# zx81_SD_10.net
KiCad netlist of a schematic drawn in EAGLE
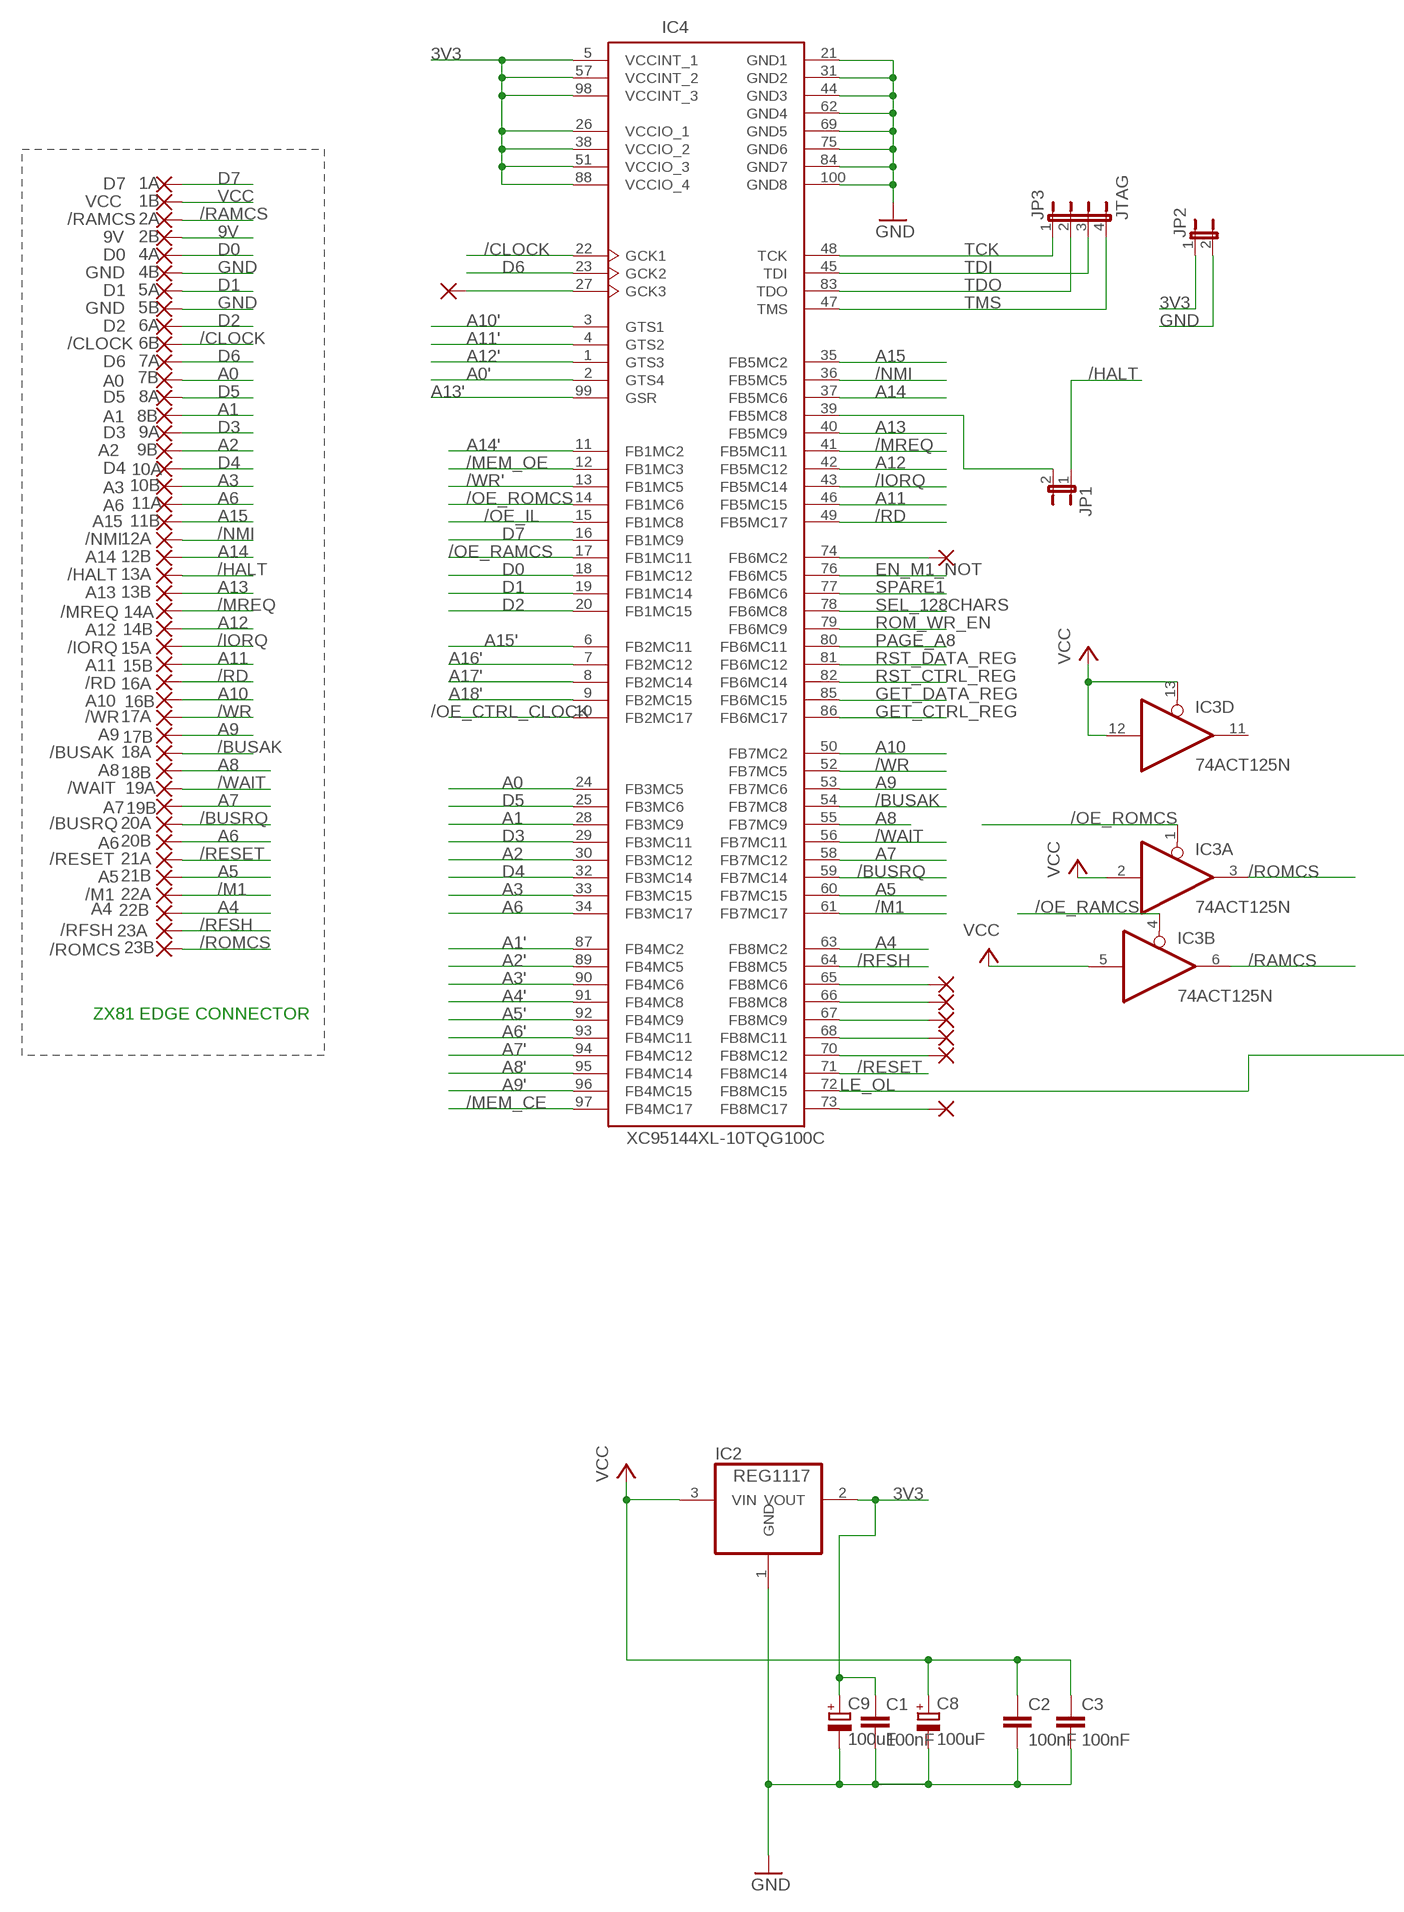
[diagram p0: schematic, sheet 1, part 1 of 2]
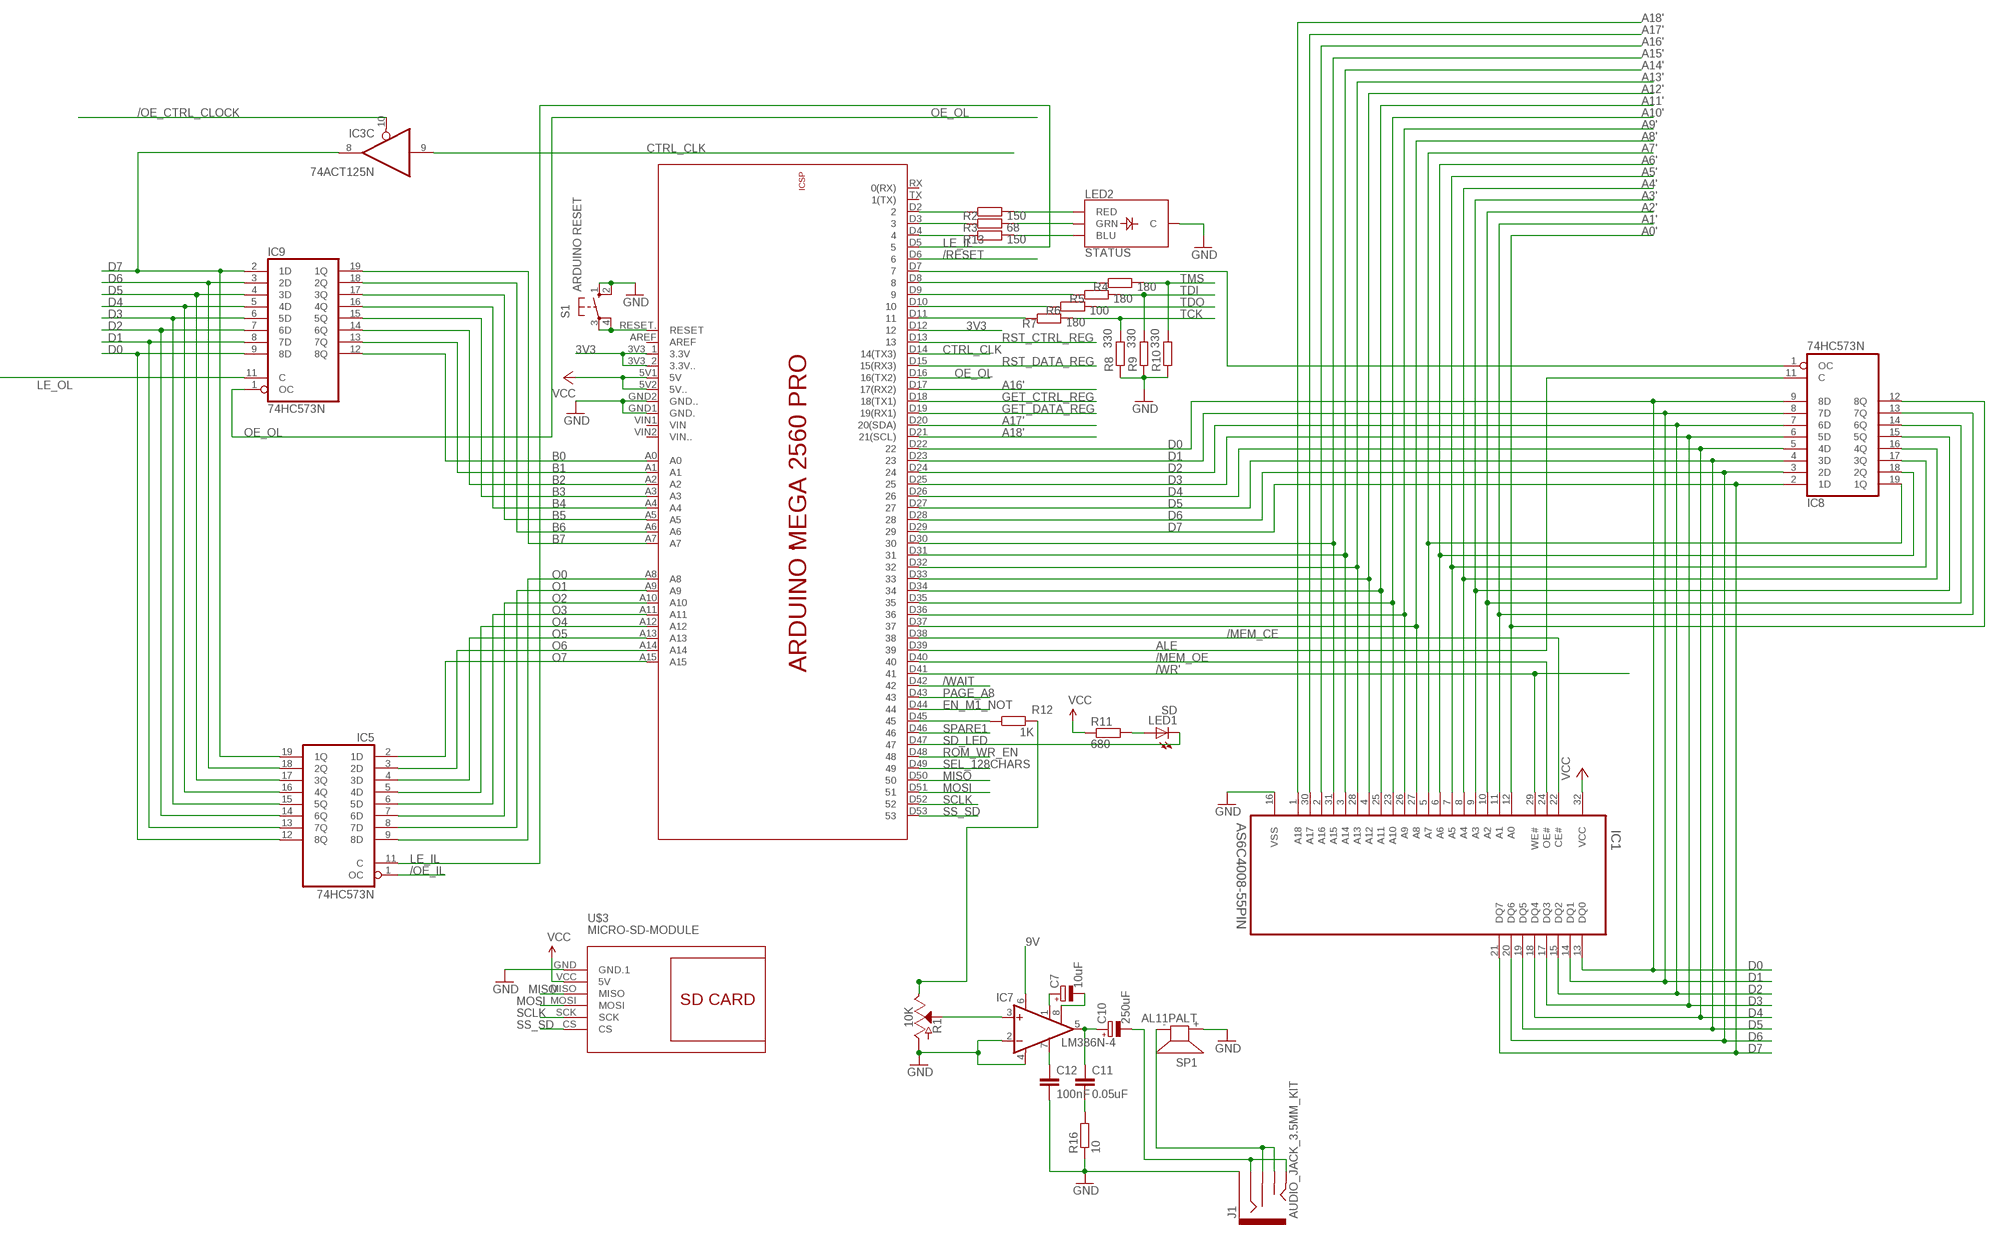
[diagram p1: schematic, sheet 1, part 2 of 2]

(export (version "E")
  (design (tool "Eeschema 10.0.6"))
  (components
    (comp (ref "1A")
      (value "D7")
      (footprint "eagle-import:EDGEPIN")
      (libsource (lib "eagle-import") (part "SMD2EDGEPIN"))
    )
    (comp (ref "1B")
      (value "VCC")
      (footprint "eagle-import:EDGEPIN")
      (libsource (lib "eagle-import") (part "SMD2EDGEPIN"))
    )
    (comp (ref "2A")
      (value "/RAMCS")
      (footprint "eagle-import:EDGEPIN")
      (libsource (lib "eagle-import") (part "SMD2EDGEPIN"))
    )
    (comp (ref "2B")
      (value "9V")
      (footprint "eagle-import:EDGEPIN")
      (libsource (lib "eagle-import") (part "SMD2EDGEPIN"))
    )
    (comp (ref "4A")
      (value "D0")
      (footprint "eagle-import:EDGEPIN")
      (libsource (lib "eagle-import") (part "SMD2EDGEPIN"))
    )
    (comp (ref "4B")
      (value "GND")
      (footprint "eagle-import:EDGEPIN")
      (libsource (lib "eagle-import") (part "SMD2EDGEPIN"))
    )
    (comp (ref "5A")
      (value "D1")
      (footprint "eagle-import:EDGEPIN")
      (libsource (lib "eagle-import") (part "SMD2EDGEPIN"))
    )
    (comp (ref "5B")
      (value "GND")
      (footprint "eagle-import:EDGEPIN")
      (libsource (lib "eagle-import") (part "SMD2EDGEPIN"))
    )
    (comp (ref "6A")
      (value "D2")
      (footprint "eagle-import:EDGEPIN")
      (libsource (lib "eagle-import") (part "SMD2EDGEPIN"))
    )
    (comp (ref "6B")
      (value "/CLOCK")
      (footprint "eagle-import:EDGEPIN")
      (libsource (lib "eagle-import") (part "SMD2EDGEPIN"))
    )
    (comp (ref "7A")
      (value "D6")
      (footprint "eagle-import:EDGEPIN")
      (libsource (lib "eagle-import") (part "SMD2EDGEPIN"))
    )
    (comp (ref "7B")
      (value "A0")
      (footprint "eagle-import:EDGEPIN")
      (libsource (lib "eagle-import") (part "SMD2EDGEPIN"))
    )
    (comp (ref "8A")
      (value "D5")
      (footprint "eagle-import:EDGEPIN")
      (libsource (lib "eagle-import") (part "SMD2EDGEPIN"))
    )
    (comp (ref "8B")
      (value "A1")
      (footprint "eagle-import:EDGEPIN")
      (libsource (lib "eagle-import") (part "SMD2EDGEPIN"))
    )
    (comp (ref "9A")
      (value "D3")
      (footprint "eagle-import:EDGEPIN")
      (libsource (lib "eagle-import") (part "SMD2EDGEPIN"))
    )
    (comp (ref "9B")
      (value "A2")
      (footprint "eagle-import:EDGEPIN")
      (libsource (lib "eagle-import") (part "SMD2EDGEPIN"))
    )
    (comp (ref "10A")
      (value "D4")
      (footprint "eagle-import:EDGEPIN")
      (libsource (lib "eagle-import") (part "SMD2EDGEPIN"))
    )
    (comp (ref "10B")
      (value "A3")
      (footprint "eagle-import:EDGEPIN")
      (libsource (lib "eagle-import") (part "SMD2EDGEPIN"))
    )
    (comp (ref "11A")
      (value "A6")
      (footprint "eagle-import:EDGEPIN")
      (libsource (lib "eagle-import") (part "SMD2EDGEPIN"))
    )
    (comp (ref "11B")
      (value "A15")
      (footprint "eagle-import:EDGEPIN")
      (libsource (lib "eagle-import") (part "SMD2EDGEPIN"))
    )
    (comp (ref "12A")
      (value "/NMI")
      (footprint "eagle-import:EDGEPIN")
      (libsource (lib "eagle-import") (part "SMD2EDGEPIN"))
    )
    (comp (ref "12B")
      (value "A14")
      (footprint "eagle-import:EDGEPIN")
      (libsource (lib "eagle-import") (part "SMD2EDGEPIN"))
    )
    (comp (ref "13A")
      (value "/HALT")
      (footprint "eagle-import:EDGEPIN")
      (libsource (lib "eagle-import") (part "SMD2EDGEPIN"))
    )
    (comp (ref "13B")
      (value "A13")
      (footprint "eagle-import:EDGEPIN")
      (libsource (lib "eagle-import") (part "SMD2EDGEPIN"))
    )
    (comp (ref "14A")
      (value "/MREQ")
      (footprint "eagle-import:EDGEPIN")
      (libsource (lib "eagle-import") (part "SMD2EDGEPIN"))
    )
    (comp (ref "14B")
      (value "A12")
      (footprint "eagle-import:EDGEPIN")
      (libsource (lib "eagle-import") (part "SMD2EDGEPIN"))
    )
    (comp (ref "15A")
      (value "/IORQ")
      (footprint "eagle-import:EDGEPIN")
      (libsource (lib "eagle-import") (part "SMD2EDGEPIN"))
    )
    (comp (ref "15B")
      (value "A11")
      (footprint "eagle-import:EDGEPIN")
      (libsource (lib "eagle-import") (part "SMD2EDGEPIN"))
    )
    (comp (ref "16A")
      (value "/RD")
      (footprint "eagle-import:EDGEPIN")
      (libsource (lib "eagle-import") (part "SMD2EDGEPIN"))
    )
    (comp (ref "16B")
      (value "A10")
      (footprint "eagle-import:EDGEPIN")
      (libsource (lib "eagle-import") (part "SMD2EDGEPIN"))
    )
    (comp (ref "17A")
      (value "/WR")
      (footprint "eagle-import:EDGEPIN")
      (libsource (lib "eagle-import") (part "SMD2EDGEPIN"))
    )
    (comp (ref "17B")
      (value "A9")
      (footprint "eagle-import:EDGEPIN")
      (libsource (lib "eagle-import") (part "SMD2EDGEPIN"))
    )
    (comp (ref "18A")
      (value "/BUSAK")
      (footprint "eagle-import:EDGEPIN")
      (libsource (lib "eagle-import") (part "SMD2EDGEPIN"))
    )
    (comp (ref "18B")
      (value "A8")
      (footprint "eagle-import:EDGEPIN")
      (libsource (lib "eagle-import") (part "SMD2EDGEPIN"))
    )
    (comp (ref "19A")
      (value "/WAIT")
      (footprint "eagle-import:EDGEPIN")
      (libsource (lib "eagle-import") (part "SMD2EDGEPIN"))
    )
    (comp (ref "19B")
      (value "A7")
      (footprint "eagle-import:EDGEPIN")
      (libsource (lib "eagle-import") (part "SMD2EDGEPIN"))
    )
    (comp (ref "20A")
      (value "/BUSRQ")
      (footprint "eagle-import:EDGEPIN")
      (libsource (lib "eagle-import") (part "SMD2EDGEPIN"))
    )
    (comp (ref "20B")
      (value "A6")
      (footprint "eagle-import:EDGEPIN")
      (libsource (lib "eagle-import") (part "SMD2EDGEPIN"))
    )
    (comp (ref "21A")
      (value "/RESET")
      (footprint "eagle-import:EDGEPIN")
      (libsource (lib "eagle-import") (part "SMD2EDGEPIN"))
    )
    (comp (ref "21B")
      (value "A5")
      (footprint "eagle-import:EDGEPIN")
      (libsource (lib "eagle-import") (part "SMD2EDGEPIN"))
    )
    (comp (ref "22A")
      (value "/M1")
      (footprint "eagle-import:EDGEPIN")
      (libsource (lib "eagle-import") (part "SMD2EDGEPIN"))
    )
    (comp (ref "22B")
      (value "A4")
      (footprint "eagle-import:EDGEPIN")
      (libsource (lib "eagle-import") (part "SMD2EDGEPIN"))
    )
    (comp (ref "23A")
      (value "/RFSH")
      (footprint "eagle-import:EDGEPIN")
      (libsource (lib "eagle-import") (part "SMD2EDGEPIN"))
    )
    (comp (ref "23B")
      (value "/ROMCS")
      (footprint "eagle-import:EDGEPIN")
      (libsource (lib "eagle-import") (part "SMD2EDGEPIN"))
    )
    (comp (ref "C1")
      (value "100nF")
      (footprint "eagle-import:C025-040X050")
      (libsource (lib "eagle-import") (part "C-EU025-040X050"))
    )
    (comp (ref "C2")
      (value "100nF")
      (footprint "eagle-import:C025-040X050")
      (libsource (lib "eagle-import") (part "C-EU025-040X050"))
    )
    (comp (ref "C3")
      (value "100nF")
      (footprint "eagle-import:C025-040X050")
      (libsource (lib "eagle-import") (part "C-EU025-040X050"))
    )
    (comp (ref "C7")
      (value "10uF")
      (footprint "eagle-import:E2-5")
      (libsource (lib "eagle-import") (part "CPOL-EUE2-5"))
    )
    (comp (ref "C8")
      (value "100uF")
      (footprint "eagle-import:E2-5")
      (libsource (lib "eagle-import") (part "CPOL-EUE2-5"))
    )
    (comp (ref "C9")
      (value "100uF")
      (footprint "eagle-import:E2-5")
      (libsource (lib "eagle-import") (part "CPOL-EUE2-5"))
    )
    (comp (ref "C10")
      (value "250uF")
      (footprint "eagle-import:E2-5")
      (libsource (lib "eagle-import") (part "CPOL-EUE2-5"))
    )
    (comp (ref "C11")
      (value "0.05uF")
      (footprint "eagle-import:C025-040X050")
      (libsource (lib "eagle-import") (part "C-EU025-040X050"))
    )
    (comp (ref "C12")
      (value "100nF")
      (footprint "eagle-import:C025-040X050")
      (libsource (lib "eagle-import") (part "C-EU025-040X050"))
    )
    (comp (ref "IC1")
      (value "AS6C4008-55PIN")
      (footprint "eagle-import:DIP1524W45P254L4203H406Q32")
      (fields (field (name "MF") "Alliance"))
      (libsource (lib "eagle-import") (part "AS6C4008-55PIN"))
    )
    (comp (ref "IC2")
      (value "REG1117")
      (footprint "eagle-import:SOT223")
      (libsource (lib "eagle-import") (part "REG1117"))
    )
    (comp (ref "IC3")
      (value "74ACT125N")
      (footprint "eagle-import:DIL14")
      (libsource (lib "eagle-import") (part "74125NACT"))
    )
    (comp (ref "IC4")
      (value "XC95144XL-10TQG100C")
      (footprint "eagle-import:TQFP100")
      (fields (field (name "MF") "Xilinx Inc."))
      (libsource (lib "eagle-import") (part "XC95144XL-10TQG100C"))
    )
    (comp (ref "IC5")
      (value "74HC573N")
      (footprint "eagle-import:DIL20")
      (libsource (lib "eagle-import") (part "74573NHC"))
    )
    (comp (ref "IC7")
      (value "LM386N-4")
      (footprint "eagle-import:DIL08")
      (libsource (lib "eagle-import") (part "LM386?-N4"))
    )
    (comp (ref "IC8")
      (value "74HC573N")
      (footprint "eagle-import:DIL20")
      (libsource (lib "eagle-import") (part "74573NHC"))
    )
    (comp (ref "IC9")
      (value "74HC573N")
      (footprint "eagle-import:DIL20")
      (libsource (lib "eagle-import") (part "74573NHC"))
    )
    (comp (ref "J1")
      (value "AUDIO_JACK_3.5MM_KIT")
      (footprint "eagle-import:AUDIO-JACK-KIT")
      (libsource (lib "eagle-import") (part "AUDIO_JACK_3.5MM_KIT"))
    )
    (comp (ref "JP1")
      (value "JP1E")
      (footprint "eagle-import:JP1")
      (libsource (lib "eagle-import") (part "JP1E"))
    )
    (comp (ref "JP2")
      (value "JP1E")
      (footprint "eagle-import:JP1")
      (libsource (lib "eagle-import") (part "JP1E"))
    )
    (comp (ref "JP3")
      (value "JTAG")
      (footprint "eagle-import:JP4")
      (libsource (lib "eagle-import") (part "JP4E"))
    )
    (comp (ref "LED1")
      (value "SD")
      (footprint "eagle-import:LED5MM")
      (libsource (lib "eagle-import") (part "LED5MM"))
    )
    (comp (ref "LED2")
      (value "STATUS")
      (footprint "eagle-import:LED-RGB-THRU")
      (libsource (lib "eagle-import") (part "LED-RGB-CCDIFFUSE"))
    )
    (comp (ref "PAD1")
      (value "1,6/0,8")
      (footprint "eagle-import:1,6_0,8")
      (libsource (lib "eagle-import") (part "1,6/0,8"))
    )
    (comp (ref "PAD2")
      (value "1,6/0,8")
      (footprint "eagle-import:1,6_0,8")
      (libsource (lib "eagle-import") (part "1,6/0,8"))
    )
    (comp (ref "PAD3")
      (value "1,6/0,8")
      (footprint "eagle-import:1,6_0,8")
      (libsource (lib "eagle-import") (part "1,6/0,8"))
    )
    (comp (ref "PAD4")
      (value "1,6/0,8")
      (footprint "eagle-import:1,6_0,8")
      (libsource (lib "eagle-import") (part "1,6/0,8"))
    )
    (comp (ref "PAD5")
      (value "1,6/0,8")
      (footprint "eagle-import:1,6_0,8")
      (libsource (lib "eagle-import") (part "1,6/0,8"))
    )
    (comp (ref "PAD6")
      (value "1,6/0,8")
      (footprint "eagle-import:1,6_0,8")
      (libsource (lib "eagle-import") (part "1,6/0,8"))
    )
    (comp (ref "PAD7")
      (value "1,6/0,8")
      (footprint "eagle-import:1,6_0,8")
      (libsource (lib "eagle-import") (part "1,6/0,8"))
    )
    (comp (ref "PAD8")
      (value "1,6/0,8")
      (footprint "eagle-import:1,6_0,8")
      (libsource (lib "eagle-import") (part "1,6/0,8"))
    )
    (comp (ref "R1")
      (value "10K")
      (footprint "eagle-import:POT-WHEEL")
      (libsource (lib "eagle-import") (part "POT"))
    )
    (comp (ref "R2")
      (value "150")
      (footprint "eagle-import:0204_7")
      (libsource (lib "eagle-import") (part "rcl_334_R-EU_0204/7"))
    )
    (comp (ref "R3")
      (value "68")
      (footprint "eagle-import:0204_7")
      (libsource (lib "eagle-import") (part "rcl_334_R-EU_0204/7"))
    )
    (comp (ref "R4")
      (value "180")
      (footprint "eagle-import:0204_7")
      (libsource (lib "eagle-import") (part "rcl_334_R-EU_0204/7"))
    )
    (comp (ref "R5")
      (value "180")
      (footprint "eagle-import:0204_7")
      (libsource (lib "eagle-import") (part "rcl_334_R-EU_0204/7"))
    )
    (comp (ref "R6")
      (value "100")
      (footprint "eagle-import:0204_7")
      (libsource (lib "eagle-import") (part "rcl_334_R-EU_0204/7"))
    )
    (comp (ref "R7")
      (value "180")
      (footprint "eagle-import:0204_7")
      (libsource (lib "eagle-import") (part "rcl_334_R-EU_0204/7"))
    )
    (comp (ref "R8")
      (value "330")
      (footprint "eagle-import:0204_7")
      (libsource (lib "eagle-import") (part "rcl_334_R-EU_0204/7"))
    )
    (comp (ref "R9")
      (value "330")
      (footprint "eagle-import:0204_7")
      (libsource (lib "eagle-import") (part "rcl_334_R-EU_0204/7"))
    )
    (comp (ref "R10")
      (value "330")
      (footprint "eagle-import:0204_7")
      (libsource (lib "eagle-import") (part "rcl_334_R-EU_0204/7"))
    )
    (comp (ref "R11")
      (value "680")
      (footprint "eagle-import:0204_7")
      (libsource (lib "eagle-import") (part "R-EU_0204/7"))
    )
    (comp (ref "R12")
      (value "1K")
      (footprint "eagle-import:0204_7")
      (libsource (lib "eagle-import") (part "R-EU_0204/7"))
    )
    (comp (ref "R13")
      (value "150")
      (footprint "eagle-import:0204_7")
      (libsource (lib "eagle-import") (part "rcl_334_R-EU_0204/7"))
    )
    (comp (ref "R16")
      (value "10")
      (footprint "eagle-import:0204_7")
      (libsource (lib "eagle-import") (part "R-EU_0204/7"))
    )
    (comp (ref "S1")
      (value "ARDUINO RESET")
      (footprint "eagle-import:B3F-10XX")
      (fields (field (name "MPN") "B3F-1000"))
      (libsource (lib "eagle-import") (part "10-XX"))
    )
    (comp (ref "SP1")
      (value "AL11PALT")
      (footprint "eagle-import:ALT")
      (libsource (lib "eagle-import") (part "AL11PALT"))
    )
    (comp (ref "U$2")
      (value "ARDUINO_MEGA2560_PRO")
      (footprint "eagle-import:ARDUINO_MEGA2560_PRO")
      (libsource (lib "eagle-import") (part "ARDUINO_MEGA2560_PRO"))
    )
    (comp (ref "U$3")
      (value "MICRO-SD-MODULE")
      (footprint "eagle-import:MICROSD-MODULE")
      (libsource (lib "eagle-import") (part "MICRO-SD-MODULE"))
    )
  )
  (nets
    (net (code "1") (name "/3V3") (class "Default")
      (node (ref "C1") (pin "1") (pinfunction "1_1") (pintype "passive"))
      (node (ref "C9") (pin "+") (pinfunction "+_+") (pintype "passive"))
      (node (ref "IC2") (pin "2") (pinfunction "VOUT_2") (pintype "output"))
      (node (ref "IC4") (pin "26") (pinfunction "VCCIO_1_26") (pintype "power_in"))
      (node (ref "IC4") (pin "38") (pinfunction "VCCIO_2_38") (pintype "power_in"))
      (node (ref "IC4") (pin "5") (pinfunction "VCCINT_1_5") (pintype "power_in"))
      (node (ref "IC4") (pin "51") (pinfunction "VCCIO_3_51") (pintype "power_in"))
      (node (ref "IC4") (pin "57") (pinfunction "VCCINT_2_57") (pintype "power_in"))
      (node (ref "IC4") (pin "88") (pinfunction "VCCIO_4_88") (pintype "power_in"))
      (node (ref "IC4") (pin "98") (pinfunction "VCCINT_3_98") (pintype "power_in"))
      (node (ref "JP2") (pin "1") (pinfunction "1_1") (pintype "passive"))
      (node (ref "U$2") (pin "3V3_1") (pinfunction "3.3V_3V3_1") (pintype "bidirectional"))
      (node (ref "U$2") (pin "3V3_2") (pinfunction "3.3V.._3V3_2") (pintype "bidirectional"))
      (node (ref "U$2") (pin "D12") (pinfunction "12_D12") (pintype "bidirectional"))
    )
    (net (code "2") (name "/9V") (class "Default")
      (node (ref "2B") (pin "1") (pinfunction "P_1") (pintype "passive"))
      (node (ref "IC7") (pin "6") (pinfunction "VS_6") (pintype "power_in"))
    )
    (net (code "3") (name "/A0") (class "Default")
      (node (ref "7B") (pin "1") (pinfunction "P_1") (pintype "passive"))
      (node (ref "IC4") (pin "24") (pinfunction "FB3MC5_24") (pintype "bidirectional"))
    )
    (net (code "4") (name "/A0'") (class "Default")
      (node (ref "IC1") (pin "12") (pinfunction "A0_12") (pintype "input"))
      (node (ref "IC4") (pin "2") (pinfunction "GTS4_2") (pintype "bidirectional"))
      (node (ref "IC8") (pin "12") (pinfunction "8Q_12") (pintype "tri_state"))
    )
    (net (code "5") (name "/A1") (class "Default")
      (node (ref "8B") (pin "1") (pinfunction "P_1") (pintype "passive"))
      (node (ref "IC4") (pin "28") (pinfunction "FB3MC9_28") (pintype "bidirectional"))
    )
    (net (code "6") (name "/A1'") (class "Default")
      (node (ref "IC1") (pin "11") (pinfunction "A1_11") (pintype "input"))
      (node (ref "IC4") (pin "87") (pinfunction "FB4MC2_87") (pintype "bidirectional"))
      (node (ref "IC8") (pin "13") (pinfunction "7Q_13") (pintype "tri_state"))
    )
    (net (code "7") (name "/A2") (class "Default")
      (node (ref "9B") (pin "1") (pinfunction "P_1") (pintype "passive"))
      (node (ref "IC4") (pin "30") (pinfunction "FB3MC12_30") (pintype "bidirectional"))
    )
    (net (code "8") (name "/A2'") (class "Default")
      (node (ref "IC1") (pin "10") (pinfunction "A2_10") (pintype "input"))
      (node (ref "IC4") (pin "89") (pinfunction "FB4MC5_89") (pintype "bidirectional"))
      (node (ref "IC8") (pin "14") (pinfunction "6Q_14") (pintype "tri_state"))
    )
    (net (code "9") (name "/A3") (class "Default")
      (node (ref "10B") (pin "1") (pinfunction "P_1") (pintype "passive"))
      (node (ref "IC4") (pin "33") (pinfunction "FB3MC15_33") (pintype "bidirectional"))
    )
    (net (code "10") (name "/A3'") (class "Default")
      (node (ref "IC1") (pin "9") (pinfunction "A3_9") (pintype "input"))
      (node (ref "IC4") (pin "90") (pinfunction "FB4MC6_90") (pintype "bidirectional"))
      (node (ref "IC8") (pin "15") (pinfunction "5Q_15") (pintype "tri_state"))
    )
    (net (code "11") (name "/A4") (class "Default")
      (node (ref "22B") (pin "1") (pinfunction "P_1") (pintype "passive"))
      (node (ref "IC4") (pin "63") (pinfunction "FB8MC2_63") (pintype "bidirectional"))
    )
    (net (code "12") (name "/A4'") (class "Default")
      (node (ref "IC1") (pin "8") (pinfunction "A4_8") (pintype "input"))
      (node (ref "IC4") (pin "91") (pinfunction "FB4MC8_91") (pintype "bidirectional"))
      (node (ref "IC8") (pin "16") (pinfunction "4Q_16") (pintype "tri_state"))
    )
    (net (code "13") (name "/A5") (class "Default")
      (node (ref "21B") (pin "1") (pinfunction "P_1") (pintype "passive"))
      (node (ref "IC4") (pin "60") (pinfunction "FB7MC15_60") (pintype "bidirectional"))
    )
    (net (code "14") (name "/A5'") (class "Default")
      (node (ref "IC1") (pin "7") (pinfunction "A5_7") (pintype "input"))
      (node (ref "IC4") (pin "92") (pinfunction "FB4MC9_92") (pintype "bidirectional"))
      (node (ref "IC8") (pin "17") (pinfunction "3Q_17") (pintype "tri_state"))
    )
    (net (code "15") (name "/A6") (class "Default")
      (node (ref "11A") (pin "1") (pinfunction "P_1") (pintype "passive"))
      (node (ref "20B") (pin "1") (pinfunction "P_1") (pintype "passive"))
      (node (ref "IC4") (pin "34") (pinfunction "FB3MC17_34") (pintype "bidirectional"))
    )
    (net (code "16") (name "/A6'") (class "Default")
      (node (ref "IC1") (pin "6") (pinfunction "A6_6") (pintype "input"))
      (node (ref "IC4") (pin "93") (pinfunction "FB4MC11_93") (pintype "bidirectional"))
      (node (ref "IC8") (pin "18") (pinfunction "2Q_18") (pintype "tri_state"))
    )
    (net (code "17") (name "/A7") (class "Default")
      (node (ref "19B") (pin "1") (pinfunction "P_1") (pintype "passive"))
      (node (ref "IC4") (pin "58") (pinfunction "FB7MC12_58") (pintype "bidirectional"))
    )
    (net (code "18") (name "/A7'") (class "Default")
      (node (ref "IC1") (pin "5") (pinfunction "A7_5") (pintype "input"))
      (node (ref "IC4") (pin "94") (pinfunction "FB4MC12_94") (pintype "bidirectional"))
      (node (ref "IC8") (pin "19") (pinfunction "1Q_19") (pintype "tri_state"))
    )
    (net (code "19") (name "/A8") (class "Default")
      (node (ref "18B") (pin "1") (pinfunction "P_1") (pintype "passive"))
      (node (ref "IC4") (pin "55") (pinfunction "FB7MC9_55") (pintype "bidirectional"))
    )
    (net (code "20") (name "/A8'") (class "Default")
      (node (ref "IC1") (pin "27") (pinfunction "A8_27") (pintype "input"))
      (node (ref "IC4") (pin "95") (pinfunction "FB4MC14_95") (pintype "bidirectional"))
      (node (ref "U$2") (pin "D37") (pinfunction "37_D37") (pintype "bidirectional"))
    )
    (net (code "21") (name "/A9") (class "Default")
      (node (ref "17B") (pin "1") (pinfunction "P_1") (pintype "passive"))
      (node (ref "IC4") (pin "53") (pinfunction "FB7MC6_53") (pintype "bidirectional"))
    )
    (net (code "22") (name "/A9'") (class "Default")
      (node (ref "IC1") (pin "26") (pinfunction "A9_26") (pintype "input"))
      (node (ref "IC4") (pin "96") (pinfunction "FB4MC15_96") (pintype "bidirectional"))
      (node (ref "U$2") (pin "D36") (pinfunction "36_D36") (pintype "bidirectional"))
    )
    (net (code "23") (name "/A10") (class "Default")
      (node (ref "16B") (pin "1") (pinfunction "P_1") (pintype "passive"))
      (node (ref "IC4") (pin "50") (pinfunction "FB7MC2_50") (pintype "bidirectional"))
    )
    (net (code "24") (name "/A10'") (class "Default")
      (node (ref "IC1") (pin "23") (pinfunction "A10_23") (pintype "input"))
      (node (ref "IC4") (pin "3") (pinfunction "GTS1_3") (pintype "bidirectional"))
      (node (ref "U$2") (pin "D35") (pinfunction "35_D35") (pintype "bidirectional"))
    )
    (net (code "25") (name "/A11") (class "Default")
      (node (ref "15B") (pin "1") (pinfunction "P_1") (pintype "passive"))
      (node (ref "IC4") (pin "46") (pinfunction "FB5MC15_46") (pintype "bidirectional"))
    )
    (net (code "26") (name "/A11'") (class "Default")
      (node (ref "IC1") (pin "25") (pinfunction "A11_25") (pintype "input"))
      (node (ref "IC4") (pin "4") (pinfunction "GTS2_4") (pintype "bidirectional"))
      (node (ref "U$2") (pin "D34") (pinfunction "34_D34") (pintype "bidirectional"))
    )
    (net (code "27") (name "/A12") (class "Default")
      (node (ref "14B") (pin "1") (pinfunction "P_1") (pintype "passive"))
      (node (ref "IC4") (pin "42") (pinfunction "FB5MC12_42") (pintype "bidirectional"))
    )
    (net (code "28") (name "/A12'") (class "Default")
      (node (ref "IC1") (pin "4") (pinfunction "A12_4") (pintype "input"))
      (node (ref "IC4") (pin "1") (pinfunction "GTS3_1") (pintype "bidirectional"))
      (node (ref "U$2") (pin "D33") (pinfunction "33_D33") (pintype "bidirectional"))
    )
    (net (code "29") (name "/A13") (class "Default")
      (node (ref "13B") (pin "1") (pinfunction "P_1") (pintype "passive"))
      (node (ref "IC4") (pin "40") (pinfunction "FB5MC9_40") (pintype "bidirectional"))
    )
    (net (code "30") (name "/A13'") (class "Default")
      (node (ref "IC1") (pin "28") (pinfunction "A13_28") (pintype "input"))
      (node (ref "IC4") (pin "99") (pinfunction "GSR_99") (pintype "bidirectional"))
      (node (ref "U$2") (pin "D32") (pinfunction "32_D32") (pintype "bidirectional"))
    )
    (net (code "31") (name "/A14") (class "Default")
      (node (ref "12B") (pin "1") (pinfunction "P_1") (pintype "passive"))
      (node (ref "IC4") (pin "37") (pinfunction "FB5MC6_37") (pintype "bidirectional"))
    )
    (net (code "32") (name "/A14'") (class "Default")
      (node (ref "IC1") (pin "3") (pinfunction "A14_3") (pintype "input"))
      (node (ref "IC4") (pin "11") (pinfunction "FB1MC2_11") (pintype "bidirectional"))
      (node (ref "U$2") (pin "D31") (pinfunction "31_D31") (pintype "bidirectional"))
    )
    (net (code "33") (name "/A15") (class "Default")
      (node (ref "11B") (pin "1") (pinfunction "P_1") (pintype "passive"))
      (node (ref "IC4") (pin "35") (pinfunction "FB5MC2_35") (pintype "bidirectional"))
    )
    (net (code "34") (name "/A15'") (class "Default")
      (node (ref "IC1") (pin "31") (pinfunction "A15_31") (pintype "input"))
      (node (ref "IC4") (pin "6") (pinfunction "FB2MC11_6") (pintype "bidirectional"))
      (node (ref "U$2") (pin "D30") (pinfunction "30_D30") (pintype "bidirectional"))
    )
    (net (code "35") (name "/A16'") (class "Default")
      (node (ref "IC1") (pin "2") (pinfunction "A16_2") (pintype "input"))
      (node (ref "IC4") (pin "7") (pinfunction "FB2MC12_7") (pintype "bidirectional"))
      (node (ref "U$2") (pin "D17") (pinfunction "17(RX2)_D17") (pintype "bidirectional"))
    )
    (net (code "36") (name "/A17'") (class "Default")
      (node (ref "IC1") (pin "30") (pinfunction "A17_30") (pintype "input"))
      (node (ref "IC4") (pin "8") (pinfunction "FB2MC14_8") (pintype "bidirectional"))
      (node (ref "U$2") (pin "D20") (pinfunction "20(SDA)_D20") (pintype "bidirectional"))
    )
    (net (code "37") (name "/A18'") (class "Default")
      (node (ref "IC1") (pin "1") (pinfunction "A18_1") (pintype "input"))
      (node (ref "IC4") (pin "9") (pinfunction "FB2MC15_9") (pintype "bidirectional"))
      (node (ref "U$2") (pin "D21") (pinfunction "21(SCL)_D21") (pintype "bidirectional"))
    )
    (net (code "38") (name "/ALE") (class "Default")
      (node (ref "IC8") (pin "11") (pinfunction "C_11") (pintype "input"))
      (node (ref "U$2") (pin "D39") (pinfunction "39_D39") (pintype "bidirectional"))
    )
    (net (code "39") (name "/B0") (class "Default")
      (node (ref "IC9") (pin "19") (pinfunction "1Q_19") (pintype "tri_state"))
      (node (ref "U$2") (pin "A7") (pinfunction "A7_A7") (pintype "bidirectional"))
    )
    (net (code "40") (name "/B1") (class "Default")
      (node (ref "IC9") (pin "18") (pinfunction "2Q_18") (pintype "tri_state"))
      (node (ref "U$2") (pin "A6") (pinfunction "A6_A6") (pintype "bidirectional"))
    )
    (net (code "41") (name "/B2") (class "Default")
      (node (ref "IC9") (pin "17") (pinfunction "3Q_17") (pintype "tri_state"))
      (node (ref "U$2") (pin "A5") (pinfunction "A5_A5") (pintype "bidirectional"))
    )
    (net (code "42") (name "/B3") (class "Default")
      (node (ref "IC9") (pin "16") (pinfunction "4Q_16") (pintype "tri_state"))
      (node (ref "U$2") (pin "A4") (pinfunction "A4_A4") (pintype "bidirectional"))
    )
    (net (code "43") (name "/B4") (class "Default")
      (node (ref "IC9") (pin "15") (pinfunction "5Q_15") (pintype "tri_state"))
      (node (ref "U$2") (pin "A3") (pinfunction "A3_A3") (pintype "bidirectional"))
    )
    (net (code "44") (name "/B5") (class "Default")
      (node (ref "IC9") (pin "14") (pinfunction "6Q_14") (pintype "tri_state"))
      (node (ref "U$2") (pin "A2") (pinfunction "A2_A2") (pintype "bidirectional"))
    )
    (net (code "45") (name "/B6") (class "Default")
      (node (ref "IC9") (pin "13") (pinfunction "7Q_13") (pintype "tri_state"))
      (node (ref "U$2") (pin "A1") (pinfunction "A1_A1") (pintype "bidirectional"))
    )
    (net (code "46") (name "/B7") (class "Default")
      (node (ref "IC9") (pin "12") (pinfunction "8Q_12") (pintype "tri_state"))
      (node (ref "U$2") (pin "A0") (pinfunction "A0_A0") (pintype "bidirectional"))
    )
    (net (code "47") (name "/CTRL_CLK") (class "Default")
      (node (ref "IC3") (pin "9") (pinfunction "I_9") (pintype "input"))
      (node (ref "U$2") (pin "D14") (pinfunction "14(TX3)_D14") (pintype "bidirectional"))
    )
    (net (code "48") (name "/D0") (class "Default")
      (node (ref "4A") (pin "1") (pinfunction "P_1") (pintype "passive"))
      (node (ref "IC1") (pin "13") (pinfunction "DQ0_13") (pintype "bidirectional"))
      (node (ref "IC4") (pin "18") (pinfunction "FB1MC12_18") (pintype "bidirectional"))
      (node (ref "IC5") (pin "12") (pinfunction "8Q_12") (pintype "tri_state"))
      (node (ref "IC8") (pin "9") (pinfunction "8D_9") (pintype "input"))
      (node (ref "IC9") (pin "9") (pinfunction "8D_9") (pintype "input"))
      (node (ref "U$2") (pin "D22") (pinfunction "22_D22") (pintype "bidirectional"))
    )
    (net (code "49") (name "/D1") (class "Default")
      (node (ref "5A") (pin "1") (pinfunction "P_1") (pintype "passive"))
      (node (ref "IC1") (pin "14") (pinfunction "DQ1_14") (pintype "bidirectional"))
      (node (ref "IC4") (pin "19") (pinfunction "FB1MC14_19") (pintype "bidirectional"))
      (node (ref "IC5") (pin "13") (pinfunction "7Q_13") (pintype "tri_state"))
      (node (ref "IC8") (pin "8") (pinfunction "7D_8") (pintype "input"))
      (node (ref "IC9") (pin "8") (pinfunction "7D_8") (pintype "input"))
      (node (ref "U$2") (pin "D23") (pinfunction "23_D23") (pintype "bidirectional"))
    )
    (net (code "50") (name "/D2") (class "Default")
      (node (ref "6A") (pin "1") (pinfunction "P_1") (pintype "passive"))
      (node (ref "IC1") (pin "15") (pinfunction "DQ2_15") (pintype "bidirectional"))
      (node (ref "IC4") (pin "20") (pinfunction "FB1MC15_20") (pintype "bidirectional"))
      (node (ref "IC5") (pin "14") (pinfunction "6Q_14") (pintype "tri_state"))
      (node (ref "IC8") (pin "7") (pinfunction "6D_7") (pintype "input"))
      (node (ref "IC9") (pin "7") (pinfunction "6D_7") (pintype "input"))
      (node (ref "U$2") (pin "D24") (pinfunction "24_D24") (pintype "bidirectional"))
    )
    (net (code "51") (name "/D3") (class "Default")
      (node (ref "9A") (pin "1") (pinfunction "P_1") (pintype "passive"))
      (node (ref "IC1") (pin "17") (pinfunction "DQ3_17") (pintype "bidirectional"))
      (node (ref "IC4") (pin "29") (pinfunction "FB3MC11_29") (pintype "bidirectional"))
      (node (ref "IC5") (pin "15") (pinfunction "5Q_15") (pintype "tri_state"))
      (node (ref "IC8") (pin "6") (pinfunction "5D_6") (pintype "input"))
      (node (ref "IC9") (pin "6") (pinfunction "5D_6") (pintype "input"))
      (node (ref "U$2") (pin "D25") (pinfunction "25_D25") (pintype "bidirectional"))
    )
    (net (code "52") (name "/D4") (class "Default")
      (node (ref "10A") (pin "1") (pinfunction "P_1") (pintype "passive"))
      (node (ref "IC1") (pin "18") (pinfunction "DQ4_18") (pintype "bidirectional"))
      (node (ref "IC4") (pin "32") (pinfunction "FB3MC14_32") (pintype "bidirectional"))
      (node (ref "IC5") (pin "16") (pinfunction "4Q_16") (pintype "tri_state"))
      (node (ref "IC8") (pin "5") (pinfunction "4D_5") (pintype "input"))
      (node (ref "IC9") (pin "5") (pinfunction "4D_5") (pintype "input"))
      (node (ref "U$2") (pin "D26") (pinfunction "26_D26") (pintype "bidirectional"))
    )
    (net (code "53") (name "/D5") (class "Default")
      (node (ref "8A") (pin "1") (pinfunction "P_1") (pintype "passive"))
      (node (ref "IC1") (pin "19") (pinfunction "DQ5_19") (pintype "bidirectional"))
      (node (ref "IC4") (pin "25") (pinfunction "FB3MC6_25") (pintype "bidirectional"))
      (node (ref "IC5") (pin "17") (pinfunction "3Q_17") (pintype "tri_state"))
      (node (ref "IC8") (pin "4") (pinfunction "3D_4") (pintype "input"))
      (node (ref "IC9") (pin "4") (pinfunction "3D_4") (pintype "input"))
      (node (ref "U$2") (pin "D27") (pinfunction "27_D27") (pintype "bidirectional"))
    )
    (net (code "54") (name "/D6") (class "Default")
      (node (ref "7A") (pin "1") (pinfunction "P_1") (pintype "passive"))
      (node (ref "IC1") (pin "20") (pinfunction "DQ6_20") (pintype "bidirectional"))
      (node (ref "IC4") (pin "23") (pinfunction "GCK2_23") (pintype "bidirectional"))
      (node (ref "IC5") (pin "18") (pinfunction "2Q_18") (pintype "tri_state"))
      (node (ref "IC8") (pin "3") (pinfunction "2D_3") (pintype "input"))
      (node (ref "IC9") (pin "3") (pinfunction "2D_3") (pintype "input"))
      (node (ref "U$2") (pin "D28") (pinfunction "28_D28") (pintype "bidirectional"))
    )
    (net (code "55") (name "/D7") (class "Default")
      (node (ref "1A") (pin "1") (pinfunction "P_1") (pintype "passive"))
      (node (ref "IC1") (pin "21") (pinfunction "DQ7_21") (pintype "bidirectional"))
      (node (ref "IC3") (pin "8") (pinfunction "O_8") (pintype "tri_state"))
      (node (ref "IC4") (pin "16") (pinfunction "FB1MC9_16") (pintype "bidirectional"))
      (node (ref "IC5") (pin "19") (pinfunction "1Q_19") (pintype "tri_state"))
      (node (ref "IC8") (pin "2") (pinfunction "1D_2") (pintype "input"))
      (node (ref "IC9") (pin "2") (pinfunction "1D_2") (pintype "input"))
      (node (ref "U$2") (pin "D29") (pinfunction "29_D29") (pintype "bidirectional"))
    )
    (net (code "56") (name "/EN_M1_NOT") (class "Default")
      (node (ref "IC4") (pin "76") (pinfunction "FB6MC5_76") (pintype "bidirectional"))
      (node (ref "U$2") (pin "D44") (pinfunction "44_D44") (pintype "bidirectional"))
    )
    (net (code "57") (name "/GET_CTRL_REG") (class "Default")
      (node (ref "IC4") (pin "86") (pinfunction "FB6MC17_86") (pintype "bidirectional"))
      (node (ref "U$2") (pin "D18") (pinfunction "18(TX1)_D18") (pintype "bidirectional"))
    )
    (net (code "58") (name "/GET_DATA_REG") (class "Default")
      (node (ref "IC4") (pin "85") (pinfunction "FB6MC15_85") (pintype "bidirectional"))
      (node (ref "U$2") (pin "D19") (pinfunction "19(RX1)_D19") (pintype "bidirectional"))
    )
    (net (code "59") (name "/LE_IL") (class "Default")
      (node (ref "IC5") (pin "11") (pinfunction "C_11") (pintype "input"))
      (node (ref "U$2") (pin "D5") (pinfunction "5_D5") (pintype "bidirectional"))
    )
    (net (code "60") (name "/LE_OL") (class "Default")
      (node (ref "IC4") (pin "72") (pinfunction "FB8MC15_72") (pintype "bidirectional"))
      (node (ref "IC9") (pin "11") (pinfunction "C_11") (pintype "input"))
    )
    (net (code "61") (name "/MISO") (class "Default")
      (node (ref "U$2") (pin "D50") (pinfunction "50_D50") (pintype "bidirectional"))
      (node (ref "U$3") (pin "MISO") (pinfunction "MISO_MISO") (pintype "bidirectional"))
    )
    (net (code "62") (name "/MOSI") (class "Default")
      (node (ref "U$2") (pin "D51") (pinfunction "51_D51") (pintype "bidirectional"))
      (node (ref "U$3") (pin "MOSI") (pinfunction "MOSI_MOSI") (pintype "bidirectional"))
    )
    (net (code "63") (name "/O0") (class "Default")
      (node (ref "IC5") (pin "2") (pinfunction "1D_2") (pintype "input"))
      (node (ref "U$2") (pin "A15") (pinfunction "A15_A15") (pintype "bidirectional"))
    )
    (net (code "64") (name "/O1") (class "Default")
      (node (ref "IC5") (pin "3") (pinfunction "2D_3") (pintype "input"))
      (node (ref "U$2") (pin "A14") (pinfunction "A14_A14") (pintype "bidirectional"))
    )
    (net (code "65") (name "/O2") (class "Default")
      (node (ref "IC5") (pin "4") (pinfunction "3D_4") (pintype "input"))
      (node (ref "U$2") (pin "A13") (pinfunction "A13_A13") (pintype "bidirectional"))
    )
    (net (code "66") (name "/O3") (class "Default")
      (node (ref "IC5") (pin "5") (pinfunction "4D_5") (pintype "input"))
      (node (ref "U$2") (pin "A12") (pinfunction "A12_A12") (pintype "bidirectional"))
    )
    (net (code "67") (name "/O4") (class "Default")
      (node (ref "IC5") (pin "6") (pinfunction "5D_6") (pintype "input"))
      (node (ref "U$2") (pin "A11") (pinfunction "A11_A11") (pintype "bidirectional"))
    )
    (net (code "68") (name "/O5") (class "Default")
      (node (ref "IC5") (pin "7") (pinfunction "6D_7") (pintype "input"))
      (node (ref "U$2") (pin "A10") (pinfunction "A10_A10") (pintype "bidirectional"))
    )
    (net (code "69") (name "/O6") (class "Default")
      (node (ref "IC5") (pin "8") (pinfunction "7D_8") (pintype "input"))
      (node (ref "U$2") (pin "A9") (pinfunction "A9_A9") (pintype "bidirectional"))
    )
    (net (code "70") (name "/O7") (class "Default")
      (node (ref "IC5") (pin "9") (pinfunction "8D_9") (pintype "input"))
      (node (ref "U$2") (pin "A8") (pinfunction "A8_A8") (pintype "bidirectional"))
    )
    (net (code "71") (name "/OE_OL") (class "Default")
      (node (ref "IC9") (pin "1") (pinfunction "OC_1") (pintype "input"))
      (node (ref "U$2") (pin "D16") (pinfunction "16(TX2)_D16") (pintype "bidirectional"))
    )
    (net (code "72") (name "/PAGE_A8") (class "Default")
      (node (ref "IC4") (pin "80") (pinfunction "FB6MC11_80") (pintype "bidirectional"))
      (node (ref "U$2") (pin "D43") (pinfunction "43_D43") (pintype "bidirectional"))
    )
    (net (code "73") (name "/ROM_WR_EN") (class "Default")
      (node (ref "IC4") (pin "79") (pinfunction "FB6MC9_79") (pintype "bidirectional"))
      (node (ref "U$2") (pin "D48") (pinfunction "48_D48") (pintype "bidirectional"))
    )
    (net (code "74") (name "/RST_CTRL_REG") (class "Default")
      (node (ref "IC4") (pin "82") (pinfunction "FB6MC14_82") (pintype "bidirectional"))
      (node (ref "U$2") (pin "D13") (pinfunction "13_D13") (pintype "bidirectional"))
    )
    (net (code "75") (name "/RST_DATA_REG") (class "Default")
      (node (ref "IC4") (pin "81") (pinfunction "FB6MC12_81") (pintype "bidirectional"))
      (node (ref "U$2") (pin "D15") (pinfunction "15(RX3)_D15") (pintype "bidirectional"))
    )
    (net (code "76") (name "/SCLK") (class "Default")
      (node (ref "U$2") (pin "D52") (pinfunction "52_D52") (pintype "bidirectional"))
      (node (ref "U$3") (pin "SCK") (pinfunction "SCK_SCK") (pintype "bidirectional"))
    )
    (net (code "77") (name "/SD_LED") (class "Default")
      (node (ref "LED1") (pin "K") (pinfunction "C_K") (pintype "passive"))
      (node (ref "U$2") (pin "D47") (pinfunction "47_D47") (pintype "bidirectional"))
    )
    (net (code "78") (name "/SEL_128CHARS") (class "Default")
      (node (ref "IC4") (pin "78") (pinfunction "FB6MC8_78") (pintype "bidirectional"))
      (node (ref "U$2") (pin "D49") (pinfunction "49_D49") (pintype "bidirectional"))
    )
    (net (code "79") (name "/SPARE1") (class "Default")
      (node (ref "IC4") (pin "77") (pinfunction "FB6MC6_77") (pintype "bidirectional"))
      (node (ref "U$2") (pin "D46") (pinfunction "46_D46") (pintype "bidirectional"))
    )
    (net (code "80") (name "/SS_SD") (class "Default")
      (node (ref "U$2") (pin "D53") (pinfunction "53_D53") (pintype "bidirectional"))
      (node (ref "U$3") (pin "CS") (pinfunction "CS_CS") (pintype "bidirectional"))
    )
    (net (code "81") (name "/TCK") (class "Default")
      (node (ref "IC4") (pin "48") (pinfunction "TCK_48") (pintype "passive"))
      (node (ref "JP3") (pin "1") (pinfunction "1_1") (pintype "passive"))
      (node (ref "R7") (pin "2") (pinfunction "2_2") (pintype "passive"))
      (node (ref "R8") (pin "2") (pinfunction "2_2") (pintype "passive"))
    )
    (net (code "82") (name "/TDI") (class "Default")
      (node (ref "IC4") (pin "45") (pinfunction "TDI_45") (pintype "passive"))
      (node (ref "JP3") (pin "3") (pinfunction "3_3") (pintype "passive"))
      (node (ref "R5") (pin "2") (pinfunction "2_2") (pintype "passive"))
      (node (ref "R9") (pin "2") (pinfunction "2_2") (pintype "passive"))
    )
    (net (code "83") (name "/TDO") (class "Default")
      (node (ref "IC4") (pin "83") (pinfunction "TDO_83") (pintype "passive"))
      (node (ref "JP3") (pin "2") (pinfunction "2_2") (pintype "passive"))
      (node (ref "R6") (pin "2") (pinfunction "2_2") (pintype "passive"))
    )
    (net (code "84") (name "/TMS") (class "Default")
      (node (ref "IC4") (pin "47") (pinfunction "TMS_47") (pintype "passive"))
      (node (ref "JP3") (pin "4") (pinfunction "4_4") (pintype "passive"))
      (node (ref "R10") (pin "2") (pinfunction "2_2") (pintype "passive"))
      (node (ref "R4") (pin "2") (pinfunction "2_2") (pintype "passive"))
    )
    (net (code "85") (name "/{slash}BUSAK") (class "Default")
      (node (ref "18A") (pin "1") (pinfunction "P_1") (pintype "passive"))
      (node (ref "IC4") (pin "54") (pinfunction "FB7MC8_54") (pintype "bidirectional"))
    )
    (net (code "86") (name "/{slash}BUSRQ") (class "Default")
      (node (ref "20A") (pin "1") (pinfunction "P_1") (pintype "passive"))
      (node (ref "IC4") (pin "59") (pinfunction "FB7MC14_59") (pintype "bidirectional"))
    )
    (net (code "87") (name "/{slash}CLOCK") (class "Default")
      (node (ref "6B") (pin "1") (pinfunction "P_1") (pintype "passive"))
      (node (ref "IC4") (pin "22") (pinfunction "GCK1_22") (pintype "bidirectional"))
    )
    (net (code "88") (name "/{slash}HALT") (class "Default")
      (node (ref "13A") (pin "1") (pinfunction "P_1") (pintype "passive"))
      (node (ref "JP1") (pin "1") (pinfunction "1_1") (pintype "passive"))
    )
    (net (code "89") (name "/{slash}IORQ") (class "Default")
      (node (ref "15A") (pin "1") (pinfunction "P_1") (pintype "passive"))
      (node (ref "IC4") (pin "43") (pinfunction "FB5MC14_43") (pintype "bidirectional"))
    )
    (net (code "90") (name "/{slash}M1") (class "Default")
      (node (ref "22A") (pin "1") (pinfunction "P_1") (pintype "passive"))
      (node (ref "IC4") (pin "61") (pinfunction "FB7MC17_61") (pintype "bidirectional"))
    )
    (net (code "91") (name "/{slash}MEM_CE") (class "Default")
      (node (ref "IC1") (pin "22") (pinfunction "CE#_22") (pintype "input"))
      (node (ref "IC4") (pin "97") (pinfunction "FB4MC17_97") (pintype "bidirectional"))
      (node (ref "U$2") (pin "D38") (pinfunction "38_D38") (pintype "bidirectional"))
    )
    (net (code "92") (name "/{slash}MEM_OE") (class "Default")
      (node (ref "IC1") (pin "24") (pinfunction "OE#_24") (pintype "input"))
      (node (ref "IC4") (pin "12") (pinfunction "FB1MC3_12") (pintype "bidirectional"))
      (node (ref "U$2") (pin "D40") (pinfunction "40_D40") (pintype "bidirectional"))
    )
    (net (code "93") (name "/{slash}MREQ") (class "Default")
      (node (ref "14A") (pin "1") (pinfunction "P_1") (pintype "passive"))
      (node (ref "IC4") (pin "41") (pinfunction "FB5MC11_41") (pintype "bidirectional"))
    )
    (net (code "94") (name "/{slash}NMI") (class "Default")
      (node (ref "12A") (pin "1") (pinfunction "P_1") (pintype "passive"))
      (node (ref "IC4") (pin "36") (pinfunction "FB5MC5_36") (pintype "bidirectional"))
    )
    (net (code "95") (name "/{slash}OE_CTRL_CLOCK") (class "Default")
      (node (ref "IC3") (pin "10") (pinfunction "OE_10") (pintype "input"))
      (node (ref "IC4") (pin "10") (pinfunction "FB2MC17_10") (pintype "bidirectional"))
    )
    (net (code "96") (name "/{slash}OE_IL") (class "Default")
      (node (ref "IC4") (pin "15") (pinfunction "FB1MC8_15") (pintype "bidirectional"))
      (node (ref "IC5") (pin "1") (pinfunction "OC_1") (pintype "input"))
    )
    (net (code "97") (name "/{slash}OE_RAMCS") (class "Default")
      (node (ref "IC3") (pin "4") (pinfunction "OE_4") (pintype "input"))
      (node (ref "IC4") (pin "17") (pinfunction "FB1MC11_17") (pintype "bidirectional"))
    )
    (net (code "98") (name "/{slash}OE_ROMCS") (class "Default")
      (node (ref "IC3") (pin "1") (pinfunction "OE_1") (pintype "input"))
      (node (ref "IC4") (pin "14") (pinfunction "FB1MC6_14") (pintype "bidirectional"))
    )
    (net (code "99") (name "/{slash}RAMCS") (class "Default")
      (node (ref "2A") (pin "1") (pinfunction "P_1") (pintype "passive"))
      (node (ref "IC3") (pin "6") (pinfunction "O_6") (pintype "tri_state"))
    )
    (net (code "100") (name "/{slash}RD") (class "Default")
      (node (ref "16A") (pin "1") (pinfunction "P_1") (pintype "passive"))
      (node (ref "IC4") (pin "49") (pinfunction "FB5MC17_49") (pintype "bidirectional"))
    )
    (net (code "101") (name "/{slash}RESET") (class "Default")
      (node (ref "21A") (pin "1") (pinfunction "P_1") (pintype "passive"))
      (node (ref "IC4") (pin "71") (pinfunction "FB8MC14_71") (pintype "bidirectional"))
      (node (ref "U$2") (pin "D6") (pinfunction "6_D6") (pintype "bidirectional"))
    )
    (net (code "102") (name "/{slash}RFSH") (class "Default")
      (node (ref "23A") (pin "1") (pinfunction "P_1") (pintype "passive"))
      (node (ref "IC4") (pin "64") (pinfunction "FB8MC5_64") (pintype "bidirectional"))
    )
    (net (code "103") (name "/{slash}ROMCS") (class "Default")
      (node (ref "23B") (pin "1") (pinfunction "P_1") (pintype "passive"))
      (node (ref "IC3") (pin "3") (pinfunction "O_3") (pintype "tri_state"))
    )
    (net (code "104") (name "/{slash}WAIT") (class "Default")
      (node (ref "19A") (pin "1") (pinfunction "P_1") (pintype "passive"))
      (node (ref "IC4") (pin "56") (pinfunction "FB7MC11_56") (pintype "bidirectional"))
      (node (ref "U$2") (pin "D42") (pinfunction "42_D42") (pintype "bidirectional"))
    )
    (net (code "105") (name "/{slash}WR") (class "Default")
      (node (ref "17A") (pin "1") (pinfunction "P_1") (pintype "passive"))
      (node (ref "IC4") (pin "52") (pinfunction "FB7MC5_52") (pintype "bidirectional"))
    )
    (net (code "106") (name "/{slash}WR'") (class "Default")
      (node (ref "IC1") (pin "29") (pinfunction "WE#_29") (pintype "input"))
      (node (ref "IC4") (pin "13") (pinfunction "FB1MC5_13") (pintype "bidirectional"))
      (node (ref "U$2") (pin "D41") (pinfunction "41_D41") (pintype "bidirectional"))
    )
    (net (code "107") (name "GND") (class "Default")
      (node (ref "4B") (pin "1") (pinfunction "P_1") (pintype "passive"))
      (node (ref "5B") (pin "1") (pinfunction "P_1") (pintype "passive"))
      (node (ref "C1") (pin "2") (pinfunction "2_2") (pintype "passive"))
      (node (ref "C12") (pin "2") (pinfunction "2_2") (pintype "passive"))
      (node (ref "C2") (pin "2") (pinfunction "2_2") (pintype "passive"))
      (node (ref "C3") (pin "2") (pinfunction "2_2") (pintype "passive"))
      (node (ref "C8") (pin "-") (pinfunction "-_-") (pintype "passive"))
      (node (ref "C9") (pin "-") (pinfunction "-_-") (pintype "passive"))
      (node (ref "IC1") (pin "16") (pinfunction "VSS_16") (pintype "power_in"))
      (node (ref "IC2") (pin "1") (pinfunction "GND_1") (pintype "power_in"))
      (node (ref "IC4") (pin "100") (pinfunction "GND8_100") (pintype "power_in"))
      (node (ref "IC4") (pin "21") (pinfunction "GND1_21") (pintype "power_in"))
      (node (ref "IC4") (pin "31") (pinfunction "GND2_31") (pintype "power_in"))
      (node (ref "IC4") (pin "44") (pinfunction "GND3_44") (pintype "power_in"))
      (node (ref "IC4") (pin "62") (pinfunction "GND4_62") (pintype "power_in"))
      (node (ref "IC4") (pin "69") (pinfunction "GND5_69") (pintype "power_in"))
      (node (ref "IC4") (pin "75") (pinfunction "GND6_75") (pintype "power_in"))
      (node (ref "IC4") (pin "84") (pinfunction "GND7_84") (pintype "power_in"))
      (node (ref "IC7") (pin "2") (pinfunction "-IN_2") (pintype "input"))
      (node (ref "IC7") (pin "4") (pinfunction "GND_4") (pintype "power_in"))
      (node (ref "J1") (pin "SLEEVE") (pinfunction "SLEEVE_SLEEVE") (pintype "bidirectional"))
      (node (ref "JP2") (pin "2") (pinfunction "2_2") (pintype "passive"))
      (node (ref "LED2") (pin "2") (pinfunction "C_2") (pintype "bidirectional"))
      (node (ref "R1") (pin "P$1") (pinfunction "A_P$1") (pintype "passive"))
      (node (ref "R10") (pin "1") (pinfunction "1_1") (pintype "passive"))
      (node (ref "R16") (pin "1") (pinfunction "1_1") (pintype "passive"))
      (node (ref "R8") (pin "1") (pinfunction "1_1") (pintype "passive"))
      (node (ref "R9") (pin "1") (pinfunction "1_1") (pintype "passive"))
      (node (ref "S1") (pin "1") (pinfunction "S_1") (pintype "passive"))
      (node (ref "S1") (pin "2") (pinfunction "S1_2") (pintype "passive"))
      (node (ref "SP1") (pin "+") (pinfunction "1_+") (pintype "passive"))
      (node (ref "U$2") (pin "GND1") (pinfunction "GND._GND1") (pintype "bidirectional"))
      (node (ref "U$2") (pin "GND2") (pinfunction "GND.._GND2") (pintype "bidirectional"))
      (node (ref "U$3") (pin "GND") (pinfunction "GND.1_GND") (pintype "power_in"))
    )
    (net (code "108") (name "Net-(C7-Pad+)") (class "Default")
      (node (ref "C7") (pin "+") (pinfunction "+_+") (pintype "passive"))
      (node (ref "IC7") (pin "1") (pinfunction "GAIN_1") (pintype "passive"))
    )
    (net (code "109") (name "Net-(C7-Pad-)") (class "Default")
      (node (ref "C7") (pin "-") (pinfunction "-_-") (pintype "passive"))
      (node (ref "IC7") (pin "8") (pinfunction "GAIN_8") (pintype "passive"))
    )
    (net (code "110") (name "Net-(C10-Pad-)") (class "Default")
      (node (ref "C10") (pin "-") (pinfunction "-_-") (pintype "passive"))
      (node (ref "J1") (pin "RING") (pinfunction "RING_RING") (pintype "bidirectional"))
      (node (ref "J1") (pin "TIP") (pinfunction "TIP_TIP") (pintype "bidirectional"))
    )
    (net (code "111") (name "Net-(C11-Pad2)") (class "Default")
      (node (ref "C11") (pin "2") (pinfunction "2_2") (pintype "passive"))
      (node (ref "R16") (pin "2") (pinfunction "2_2") (pintype "passive"))
    )
    (net (code "112") (name "Net-(IC4-FB5MC8)") (class "Default")
      (node (ref "IC4") (pin "39") (pinfunction "FB5MC8_39") (pintype "bidirectional"))
      (node (ref "JP1") (pin "2") (pinfunction "2_2") (pintype "passive"))
    )
    (net (code "113") (name "Net-(IC4-FB6MC2)") (class "Default")
      (node (ref "IC4") (pin "74") (pinfunction "FB6MC2_74") (pintype "bidirectional"))
      (node (ref "PAD8") (pin "1") (pinfunction "P_1") (pintype "passive"))
    )
    (net (code "114") (name "Net-(IC4-FB8MC6)") (class "Default")
      (node (ref "IC4") (pin "65") (pinfunction "FB8MC6_65") (pintype "bidirectional"))
      (node (ref "PAD2") (pin "1") (pinfunction "P_1") (pintype "passive"))
    )
    (net (code "115") (name "Net-(IC4-FB8MC8)") (class "Default")
      (node (ref "IC4") (pin "66") (pinfunction "FB8MC8_66") (pintype "bidirectional"))
      (node (ref "PAD3") (pin "1") (pinfunction "P_1") (pintype "passive"))
    )
    (net (code "116") (name "Net-(IC4-FB8MC9)") (class "Default")
      (node (ref "IC4") (pin "67") (pinfunction "FB8MC9_67") (pintype "bidirectional"))
      (node (ref "PAD4") (pin "1") (pinfunction "P_1") (pintype "passive"))
    )
    (net (code "117") (name "Net-(IC4-FB8MC11)") (class "Default")
      (node (ref "IC4") (pin "68") (pinfunction "FB8MC11_68") (pintype "bidirectional"))
      (node (ref "PAD5") (pin "1") (pinfunction "P_1") (pintype "passive"))
    )
    (net (code "118") (name "Net-(IC4-FB8MC12)") (class "Default")
      (node (ref "IC4") (pin "70") (pinfunction "FB8MC12_70") (pintype "bidirectional"))
      (node (ref "PAD7") (pin "1") (pinfunction "P_1") (pintype "passive"))
    )
    (net (code "119") (name "Net-(IC4-FB8MC17)") (class "Default")
      (node (ref "IC4") (pin "73") (pinfunction "FB8MC17_73") (pintype "bidirectional"))
      (node (ref "PAD6") (pin "1") (pinfunction "P_1") (pintype "passive"))
    )
    (net (code "120") (name "Net-(IC4-GCK3)") (class "Default")
      (node (ref "IC4") (pin "27") (pinfunction "GCK3_27") (pintype "bidirectional"))
      (node (ref "PAD1") (pin "1") (pinfunction "P_1") (pintype "passive"))
    )
    (net (code "121") (name "Net-(IC7-+IN)") (class "Default")
      (node (ref "IC7") (pin "3") (pinfunction "+IN_3") (pintype "input"))
      (node (ref "R1") (pin "P$3") (pinfunction "S_P$3") (pintype "passive"))
    )
    (net (code "122") (name "Net-(IC7-BYPASS)") (class "Default")
      (node (ref "C12") (pin "1") (pinfunction "1_1") (pintype "passive"))
      (node (ref "IC7") (pin "7") (pinfunction "BYPASS_7") (pintype "passive"))
    )
    (net (code "123") (name "Net-(IC7-OUT)") (class "Default")
      (node (ref "C10") (pin "+") (pinfunction "+_+") (pintype "passive"))
      (node (ref "C11") (pin "1") (pinfunction "1_1") (pintype "passive"))
      (node (ref "IC7") (pin "5") (pinfunction "OUT_5") (pintype "output"))
    )
    (net (code "124") (name "Net-(IC8A-OC)") (class "Default")
      (node (ref "IC8") (pin "1") (pinfunction "OC_1") (pintype "input"))
      (node (ref "U$2") (pin "D7") (pinfunction "7_D7") (pintype "bidirectional"))
    )
    (net (code "125") (name "Net-(LED1-PadA)") (class "Default")
      (node (ref "LED1") (pin "A") (pinfunction "A_A") (pintype "passive"))
      (node (ref "R11") (pin "2") (pinfunction "2_2") (pintype "passive"))
    )
    (net (code "126") (name "Net-(LED2-BLU)") (class "Default")
      (node (ref "LED2") (pin "3") (pinfunction "BLU_3") (pintype "bidirectional"))
      (node (ref "R13") (pin "2") (pinfunction "2_2") (pintype "passive"))
    )
    (net (code "127") (name "Net-(LED2-GRN)") (class "Default")
      (node (ref "LED2") (pin "4") (pinfunction "GRN_4") (pintype "bidirectional"))
      (node (ref "R3") (pin "2") (pinfunction "2_2") (pintype "passive"))
    )
    (net (code "128") (name "Net-(LED2-RED)") (class "Default")
      (node (ref "LED2") (pin "1") (pinfunction "RED_1") (pintype "bidirectional"))
      (node (ref "R2") (pin "2") (pinfunction "2_2") (pintype "passive"))
    )
    (net (code "129") (name "Net-(R1-E)") (class "Default")
      (node (ref "R1") (pin "P$2") (pinfunction "E_P$2") (pintype "passive"))
      (node (ref "R12") (pin "2") (pinfunction "2_2") (pintype "passive"))
    )
    (net (code "130") (name "Net-(S1-P)") (class "Default")
      (node (ref "S1") (pin "3") (pinfunction "P_3") (pintype "passive"))
      (node (ref "S1") (pin "4") (pinfunction "P1_4") (pintype "passive"))
      (node (ref "U$2") (pin "RESET.") (pinfunction "RESET_RESET.") (pintype "bidirectional"))
    )
    (net (code "131") (name "Net-(SP1-2)") (class "Default")
      (node (ref "J1") (pin "RSH") (pinfunction "RSH_RSH") (pintype "bidirectional"))
      (node (ref "J1") (pin "TSH") (pinfunction "TSH_TSH") (pintype "bidirectional"))
      (node (ref "SP1") (pin "-") (pinfunction "2_-") (pintype "passive"))
    )
    (net (code "132") (name "Net-(U$2-2)") (class "Default")
      (node (ref "R2") (pin "1") (pinfunction "1_1") (pintype "passive"))
      (node (ref "U$2") (pin "D2") (pinfunction "2_D2") (pintype "bidirectional"))
    )
    (net (code "133") (name "Net-(U$2-3)") (class "Default")
      (node (ref "R3") (pin "1") (pinfunction "1_1") (pintype "passive"))
      (node (ref "U$2") (pin "D3") (pinfunction "3_D3") (pintype "bidirectional"))
    )
    (net (code "134") (name "Net-(U$2-4)") (class "Default")
      (node (ref "R13") (pin "1") (pinfunction "1_1") (pintype "passive"))
      (node (ref "U$2") (pin "D4") (pinfunction "4_D4") (pintype "bidirectional"))
    )
    (net (code "135") (name "Net-(U$2-8)") (class "Default")
      (node (ref "R4") (pin "1") (pinfunction "1_1") (pintype "passive"))
      (node (ref "U$2") (pin "D8") (pinfunction "8_D8") (pintype "bidirectional"))
    )
    (net (code "136") (name "Net-(U$2-9)") (class "Default")
      (node (ref "R5") (pin "1") (pinfunction "1_1") (pintype "passive"))
      (node (ref "U$2") (pin "D9") (pinfunction "9_D9") (pintype "bidirectional"))
    )
    (net (code "137") (name "Net-(U$2-10)") (class "Default")
      (node (ref "R6") (pin "1") (pinfunction "1_1") (pintype "passive"))
      (node (ref "U$2") (pin "D10") (pinfunction "10_D10") (pintype "bidirectional"))
    )
    (net (code "138") (name "Net-(U$2-11)") (class "Default")
      (node (ref "R7") (pin "1") (pinfunction "1_1") (pintype "passive"))
      (node (ref "U$2") (pin "D11") (pinfunction "11_D11") (pintype "bidirectional"))
    )
    (net (code "139") (name "Net-(U$2-45)") (class "Default")
      (node (ref "R12") (pin "1") (pinfunction "1_1") (pintype "passive"))
      (node (ref "U$2") (pin "D45") (pinfunction "45_D45") (pintype "bidirectional"))
    )
    (net (code "140") (name "VCC") (class "Default")
      (node (ref "1B") (pin "1") (pinfunction "P_1") (pintype "passive"))
      (node (ref "C2") (pin "1") (pinfunction "1_1") (pintype "passive"))
      (node (ref "C3") (pin "1") (pinfunction "1_1") (pintype "passive"))
      (node (ref "C8") (pin "+") (pinfunction "+_+") (pintype "passive"))
      (node (ref "IC1") (pin "32") (pinfunction "VCC_32") (pintype "power_in"))
      (node (ref "IC2") (pin "3") (pinfunction "VIN_3") (pintype "input"))
      (node (ref "IC3") (pin "12") (pinfunction "I_12") (pintype "input"))
      (node (ref "IC3") (pin "13") (pinfunction "OE_13") (pintype "input"))
      (node (ref "IC3") (pin "2") (pinfunction "I_2") (pintype "input"))
      (node (ref "IC3") (pin "5") (pinfunction "I_5") (pintype "input"))
      (node (ref "R11") (pin "1") (pinfunction "1_1") (pintype "passive"))
      (node (ref "U$2") (pin "5V1") (pinfunction "5V_5V1") (pintype "bidirectional"))
      (node (ref "U$2") (pin "5V2") (pinfunction "5V.._5V2") (pintype "bidirectional"))
      (node (ref "U$3") (pin "VCC") (pinfunction "5V_VCC") (pintype "power_in"))
    )
    (net (code "141") (name "unconnected-(IC3D-O-Pad11)") (class "Default")
      (node (ref "IC3") (pin "11") (pinfunction "O_11") (pintype "tri_state"))
    )
    (net (code "142") (name "unconnected-(U$2-0(RX)-PadRX)") (class "Default")
      (node (ref "U$2") (pin "RX") (pinfunction "0(RX)_RX") (pintype "bidirectional"))
    )
    (net (code "143") (name "unconnected-(U$2-1(TX)-PadTX)") (class "Default")
      (node (ref "U$2") (pin "TX") (pinfunction "1(TX)_TX") (pintype "bidirectional"))
    )
    (net (code "144") (name "unconnected-(U$2-Pad+5V_)") (class "Default")
      (node (ref "U$2") (pin "+5V_") (pinfunction "+5V__+5V_") (pintype "bidirectional"))
    )
    (net (code "145") (name "unconnected-(U$2-PadAREF)") (class "Default")
      (node (ref "U$2") (pin "AREF") (pinfunction "AREF_AREF") (pintype "bidirectional"))
    )
    (net (code "146") (name "unconnected-(U$2-PadGND__)") (class "Default")
      (node (ref "U$2") (pin "GND__") (pinfunction "GND___GND__") (pintype "bidirectional"))
    )
    (net (code "147") (name "unconnected-(U$2-PadMISO)") (class "Default")
      (node (ref "U$2") (pin "MISO") (pinfunction "MISO_MISO") (pintype "bidirectional"))
    )
    (net (code "148") (name "unconnected-(U$2-PadMOSI)") (class "Default")
      (node (ref "U$2") (pin "MOSI") (pinfunction "MOSI_MOSI") (pintype "bidirectional"))
    )
    (net (code "149") (name "unconnected-(U$2-PadSCK)") (class "Default")
      (node (ref "U$2") (pin "SCK") (pinfunction "SCK_SCK") (pintype "bidirectional"))
    )
    (net (code "150") (name "unconnected-(U$2-RESET.-PadRST)") (class "Default")
      (node (ref "U$2") (pin "RST") (pinfunction "RESET._RST") (pintype "bidirectional"))
    )
    (net (code "151") (name "unconnected-(U$2-VIN-PadVIN1)") (class "Default")
      (node (ref "U$2") (pin "VIN1") (pinfunction "VIN_VIN1") (pintype "bidirectional"))
    )
    (net (code "152") (name "unconnected-(U$2-VIN..-PadVIN2)") (class "Default")
      (node (ref "U$2") (pin "VIN2") (pinfunction "VIN.._VIN2") (pintype "bidirectional"))
    )
  )
)
